# 2xVCA.net
KiCad netlist of a schematic drawn in EAGLE
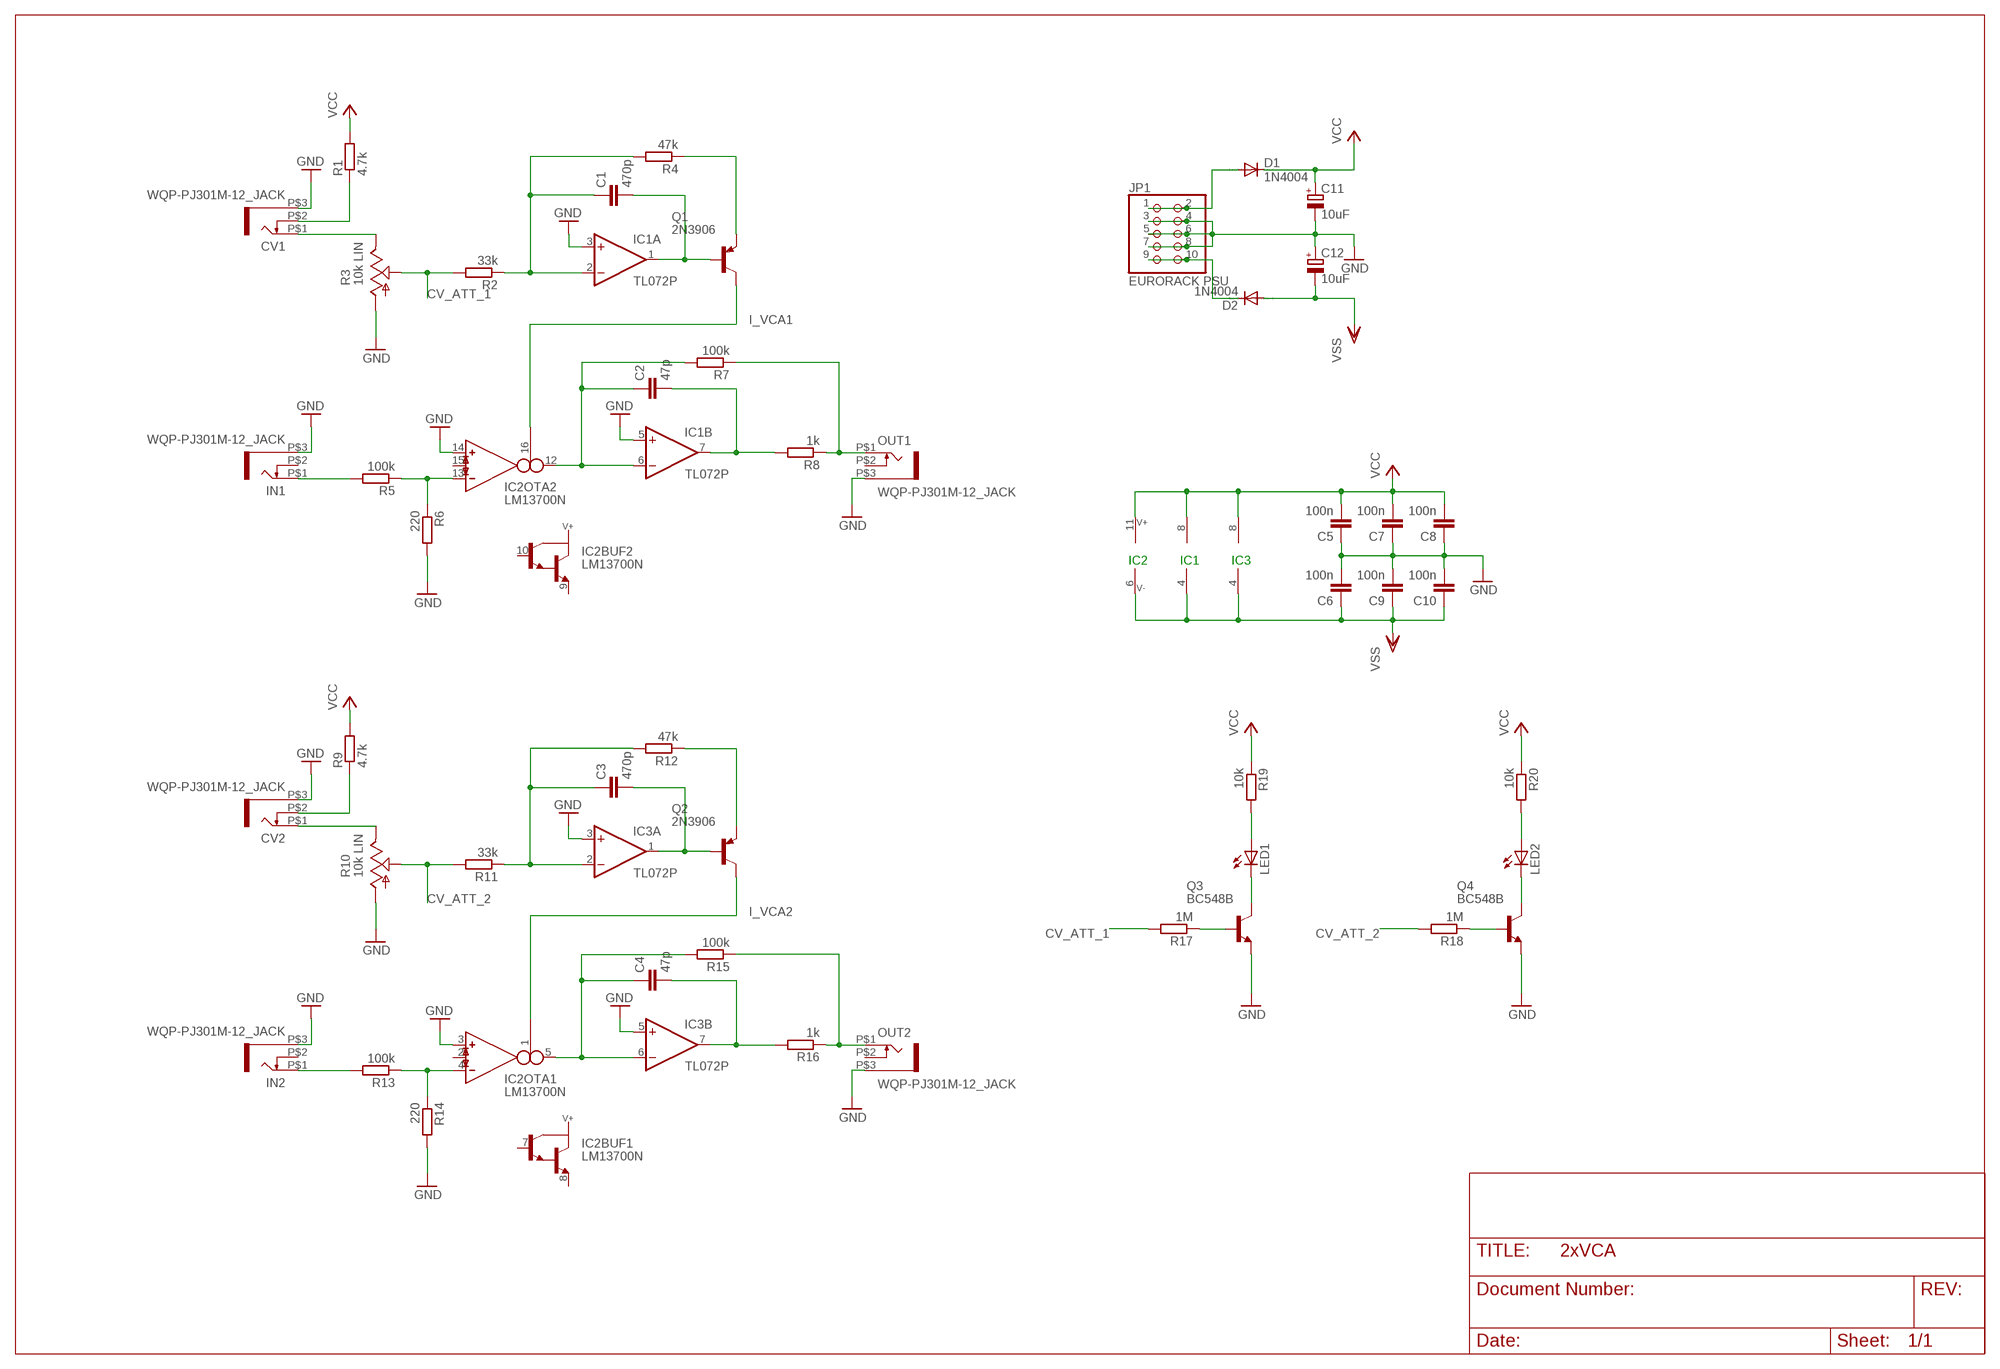
[diagram p0: schematic, sheet 1]

(export (version "E")
  (design (tool "Eeschema 10.0.6"))
  (components
    (comp (ref "C1")
      (value "470p")
      (footprint "eagle-import:C025-025X050")
      (libsource (lib "eagle-import") (part "C-EU025-025X050"))
    )
    (comp (ref "C2")
      (value "47p")
      (footprint "eagle-import:C025-025X050")
      (libsource (lib "eagle-import") (part "C-EU025-025X050"))
    )
    (comp (ref "C3")
      (value "470p")
      (footprint "eagle-import:C025-025X050")
      (libsource (lib "eagle-import") (part "C-EU025-025X050"))
    )
    (comp (ref "C4")
      (value "47p")
      (footprint "eagle-import:C025-025X050")
      (libsource (lib "eagle-import") (part "C-EU025-025X050"))
    )
    (comp (ref "C5")
      (value "100n")
      (footprint "eagle-import:C025-025X050")
      (libsource (lib "eagle-import") (part "C-EU025-025X050"))
    )
    (comp (ref "C6")
      (value "100n")
      (footprint "eagle-import:C025-025X050")
      (libsource (lib "eagle-import") (part "C-EU025-025X050"))
    )
    (comp (ref "C7")
      (value "100n")
      (footprint "eagle-import:C025-025X050")
      (libsource (lib "eagle-import") (part "C-EU025-025X050"))
    )
    (comp (ref "C8")
      (value "100n")
      (footprint "eagle-import:C025-025X050")
      (libsource (lib "eagle-import") (part "C-EU025-025X050"))
    )
    (comp (ref "C9")
      (value "100n")
      (footprint "eagle-import:C025-025X050")
      (libsource (lib "eagle-import") (part "C-EU025-025X050"))
    )
    (comp (ref "C10")
      (value "100n")
      (footprint "eagle-import:C025-025X050")
      (libsource (lib "eagle-import") (part "C-EU025-025X050"))
    )
    (comp (ref "C11")
      (value "10uF")
      (footprint "eagle-import:E2,5-5")
      (libsource (lib "eagle-import") (part "CPOL-EUE2.5-5"))
    )
    (comp (ref "C12")
      (value "10uF")
      (footprint "eagle-import:E2,5-5")
      (libsource (lib "eagle-import") (part "CPOL-EUE2.5-5"))
    )
    (comp (ref "CV1")
      (value "WQP-PJ301M-12_JACK")
      (footprint "eagle-import:WQP-PJ301M-12_JACK")
      (libsource (lib "eagle-import") (part "WQP-PJ301M-12_JACK"))
    )
    (comp (ref "CV2")
      (value "WQP-PJ301M-12_JACK")
      (footprint "eagle-import:WQP-PJ301M-12_JACK")
      (libsource (lib "eagle-import") (part "WQP-PJ301M-12_JACK"))
    )
    (comp (ref "D1")
      (value "1N4004")
      (footprint "eagle-import:DO41-10")
      (libsource (lib "eagle-import") (part "1N4004"))
    )
    (comp (ref "D2")
      (value "1N4004")
      (footprint "eagle-import:DO41-10")
      (libsource (lib "eagle-import") (part "1N4004"))
    )
    (comp (ref "IC1")
      (value "TL072P")
      (footprint "eagle-import:DIL08")
      (libsource (lib "eagle-import") (part "TL072P"))
    )
    (comp (ref "IC2")
      (value "LM13700N")
      (footprint "eagle-import:DIL16")
      (libsource (lib "eagle-import") (part "LM13700N"))
    )
    (comp (ref "IC3")
      (value "TL072P")
      (footprint "eagle-import:DIL08")
      (libsource (lib "eagle-import") (part "TL072P"))
    )
    (comp (ref "IN1")
      (value "WQP-PJ301M-12_JACK")
      (footprint "eagle-import:WQP-PJ301M-12_JACK")
      (libsource (lib "eagle-import") (part "WQP-PJ301M-12_JACK"))
    )
    (comp (ref "IN2")
      (value "WQP-PJ301M-12_JACK")
      (footprint "eagle-import:WQP-PJ301M-12_JACK")
      (libsource (lib "eagle-import") (part "WQP-PJ301M-12_JACK"))
    )
    (comp (ref "JP1")
      (value "EURORACK PSU")
      (footprint "eagle-import:2X05")
      (libsource (lib "eagle-import") (part "PINHD-2X5"))
    )
    (comp (ref "LED1")
      (value "LED3MM")
      (footprint "eagle-import:LED3MM")
      (libsource (lib "eagle-import") (part "LED3MM"))
    )
    (comp (ref "LED2")
      (value "LED3MM")
      (footprint "eagle-import:LED3MM")
      (libsource (lib "eagle-import") (part "LED3MM"))
    )
    (comp (ref "OUT1")
      (value "WQP-PJ301M-12_JACK")
      (footprint "eagle-import:WQP-PJ301M-12_JACK")
      (libsource (lib "eagle-import") (part "WQP-PJ301M-12_JACK"))
    )
    (comp (ref "OUT2")
      (value "WQP-PJ301M-12_JACK")
      (footprint "eagle-import:WQP-PJ301M-12_JACK")
      (libsource (lib "eagle-import") (part "WQP-PJ301M-12_JACK"))
    )
    (comp (ref "Q1")
      (value "2N3906")
      (footprint "eagle-import:TO92")
      (libsource (lib "eagle-import") (part "2N3906"))
    )
    (comp (ref "Q2")
      (value "2N3906")
      (footprint "eagle-import:TO92")
      (libsource (lib "eagle-import") (part "2N3906"))
    )
    (comp (ref "Q3")
      (value "BC548B")
      (footprint "eagle-import:TO92-EBC")
      (libsource (lib "eagle-import") (part "BC548B"))
    )
    (comp (ref "Q4")
      (value "BC548B")
      (footprint "eagle-import:TO92-EBC")
      (libsource (lib "eagle-import") (part "BC548B"))
    )
    (comp (ref "R1")
      (value "4.7k")
      (footprint "eagle-import:0207_2V")
      (libsource (lib "eagle-import") (part "R-EU_0207/2V"))
    )
    (comp (ref "R2")
      (value "33k")
      (footprint "eagle-import:0207_2V")
      (libsource (lib "eagle-import") (part "R-EU_0207/2V"))
    )
    (comp (ref "R3")
      (value "10k LIN")
      (footprint "eagle-import:ALPS_POT_VERTICAL")
      (libsource (lib "eagle-import") (part "POT_USVERTICAL"))
    )
    (comp (ref "R4")
      (value "47k")
      (footprint "eagle-import:0207_2V")
      (libsource (lib "eagle-import") (part "R-EU_0207/2V"))
    )
    (comp (ref "R5")
      (value "100k")
      (footprint "eagle-import:0207_2V")
      (libsource (lib "eagle-import") (part "R-EU_0207/2V"))
    )
    (comp (ref "R6")
      (value "220")
      (footprint "eagle-import:0207_2V")
      (libsource (lib "eagle-import") (part "R-EU_0207/2V"))
    )
    (comp (ref "R7")
      (value "100k")
      (footprint "eagle-import:0207_2V")
      (libsource (lib "eagle-import") (part "R-EU_0207/2V"))
    )
    (comp (ref "R8")
      (value "1k")
      (footprint "eagle-import:0207_2V")
      (libsource (lib "eagle-import") (part "R-EU_0207/2V"))
    )
    (comp (ref "R9")
      (value "4.7k")
      (footprint "eagle-import:0207_2V")
      (libsource (lib "eagle-import") (part "R-EU_0207/2V"))
    )
    (comp (ref "R10")
      (value "10k LIN")
      (footprint "eagle-import:ALPS_POT_VERTICAL")
      (libsource (lib "eagle-import") (part "POT_USVERTICAL"))
    )
    (comp (ref "R11")
      (value "33k")
      (footprint "eagle-import:0207_2V")
      (libsource (lib "eagle-import") (part "R-EU_0207/2V"))
    )
    (comp (ref "R12")
      (value "47k")
      (footprint "eagle-import:0207_2V")
      (libsource (lib "eagle-import") (part "R-EU_0207/2V"))
    )
    (comp (ref "R13")
      (value "100k")
      (footprint "eagle-import:0207_2V")
      (libsource (lib "eagle-import") (part "R-EU_0207/2V"))
    )
    (comp (ref "R14")
      (value "220")
      (footprint "eagle-import:0207_2V")
      (libsource (lib "eagle-import") (part "R-EU_0207/2V"))
    )
    (comp (ref "R15")
      (value "100k")
      (footprint "eagle-import:0207_2V")
      (libsource (lib "eagle-import") (part "R-EU_0207/2V"))
    )
    (comp (ref "R16")
      (value "1k")
      (footprint "eagle-import:0207_2V")
      (libsource (lib "eagle-import") (part "R-EU_0207/2V"))
    )
    (comp (ref "R17")
      (value "1M")
      (footprint "eagle-import:0207_2V")
      (libsource (lib "eagle-import") (part "R-EU_0207/2V"))
    )
    (comp (ref "R18")
      (value "1M")
      (footprint "eagle-import:0207_2V")
      (libsource (lib "eagle-import") (part "R-EU_0207/2V"))
    )
    (comp (ref "R19")
      (value "10k")
      (footprint "eagle-import:0207_2V")
      (libsource (lib "eagle-import") (part "R-EU_0207/2V"))
    )
    (comp (ref "R20")
      (value "10k")
      (footprint "eagle-import:0207_2V")
      (libsource (lib "eagle-import") (part "R-EU_0207/2V"))
    )
  )
  (nets
    (net (code "1") (name "/CV_ATT_1") (class "Default")
      (node (ref "R17") (pin "2") (pinfunction "2_2") (pintype "passive"))
      (node (ref "R2") (pin "2") (pinfunction "2_2") (pintype "passive"))
      (node (ref "R3") (pin "P$2") (pinfunction "S_P$2") (pintype "passive"))
    )
    (net (code "2") (name "/CV_ATT_2") (class "Default")
      (node (ref "R10") (pin "P$2") (pinfunction "S_P$2") (pintype "passive"))
      (node (ref "R11") (pin "2") (pinfunction "2_2") (pintype "passive"))
      (node (ref "R18") (pin "2") (pinfunction "2_2") (pintype "passive"))
    )
    (net (code "3") (name "/I_VCA1") (class "Default")
      (node (ref "IC2") (pin "16") (pinfunction "I_BIAS_16") (pintype "input"))
      (node (ref "Q1") (pin "1") (pinfunction "C_1") (pintype "passive"))
    )
    (net (code "4") (name "/I_VCA2") (class "Default")
      (node (ref "IC2") (pin "1") (pinfunction "I_BIAS_1") (pintype "input"))
      (node (ref "Q2") (pin "1") (pinfunction "C_1") (pintype "passive"))
    )
    (net (code "5") (name "GND") (class "Default")
      (node (ref "C10") (pin "2") (pinfunction "2_2") (pintype "passive"))
      (node (ref "C11") (pin "-") (pinfunction "-_-") (pintype "passive"))
      (node (ref "C12") (pin "+") (pinfunction "+_+") (pintype "passive"))
      (node (ref "C5") (pin "1") (pinfunction "1_1") (pintype "passive"))
      (node (ref "C6") (pin "2") (pinfunction "2_2") (pintype "passive"))
      (node (ref "C7") (pin "1") (pinfunction "1_1") (pintype "passive"))
      (node (ref "C8") (pin "1") (pinfunction "1_1") (pintype "passive"))
      (node (ref "C9") (pin "2") (pinfunction "2_2") (pintype "passive"))
      (node (ref "CV1") (pin "P$3") (pinfunction "1_P$3") (pintype "passive"))
      (node (ref "CV2") (pin "P$3") (pinfunction "1_P$3") (pintype "passive"))
      (node (ref "IC1") (pin "3") (pinfunction "+IN_3") (pintype "input"))
      (node (ref "IC1") (pin "5") (pinfunction "+IN_5") (pintype "input"))
      (node (ref "IC2") (pin "14") (pinfunction "IN_P_14") (pintype "input"))
      (node (ref "IC2") (pin "3") (pinfunction "IN_P_3") (pintype "input"))
      (node (ref "IC3") (pin "3") (pinfunction "+IN_3") (pintype "input"))
      (node (ref "IC3") (pin "5") (pinfunction "+IN_5") (pintype "input"))
      (node (ref "IN1") (pin "P$3") (pinfunction "1_P$3") (pintype "passive"))
      (node (ref "IN2") (pin "P$3") (pinfunction "1_P$3") (pintype "passive"))
      (node (ref "JP1") (pin "3") (pinfunction "3_3") (pintype "passive"))
      (node (ref "JP1") (pin "4") (pinfunction "4_4") (pintype "passive"))
      (node (ref "JP1") (pin "5") (pinfunction "5_5") (pintype "passive"))
      (node (ref "JP1") (pin "6") (pinfunction "6_6") (pintype "passive"))
      (node (ref "JP1") (pin "7") (pinfunction "7_7") (pintype "passive"))
      (node (ref "JP1") (pin "8") (pinfunction "8_8") (pintype "passive"))
      (node (ref "OUT1") (pin "P$3") (pinfunction "1_P$3") (pintype "passive"))
      (node (ref "OUT2") (pin "P$3") (pinfunction "1_P$3") (pintype "passive"))
      (node (ref "Q3") (pin "E") (pinfunction "E_E") (pintype "passive"))
      (node (ref "Q4") (pin "E") (pinfunction "E_E") (pintype "passive"))
      (node (ref "R10") (pin "P$3") (pinfunction "A_P$3") (pintype "passive"))
      (node (ref "R14") (pin "2") (pinfunction "2_2") (pintype "passive"))
      (node (ref "R3") (pin "P$3") (pinfunction "A_P$3") (pintype "passive"))
      (node (ref "R6") (pin "2") (pinfunction "2_2") (pintype "passive"))
    )
    (net (code "6") (name "Net-(CV1-2)") (class "Default")
      (node (ref "CV1") (pin "P$1") (pinfunction "2_P$1") (pintype "passive"))
      (node (ref "R3") (pin "P$1") (pinfunction "E_P$1") (pintype "passive"))
    )
    (net (code "7") (name "Net-(CV1-3)") (class "Default")
      (node (ref "CV1") (pin "P$2") (pinfunction "3_P$2") (pintype "passive"))
      (node (ref "R1") (pin "1") (pinfunction "1_1") (pintype "passive"))
    )
    (net (code "8") (name "Net-(CV2-2)") (class "Default")
      (node (ref "CV2") (pin "P$1") (pinfunction "2_P$1") (pintype "passive"))
      (node (ref "R10") (pin "P$1") (pinfunction "E_P$1") (pintype "passive"))
    )
    (net (code "9") (name "Net-(CV2-3)") (class "Default")
      (node (ref "CV2") (pin "P$2") (pinfunction "3_P$2") (pintype "passive"))
      (node (ref "R9") (pin "1") (pinfunction "1_1") (pintype "passive"))
    )
    (net (code "10") (name "Net-(D1-PadA)") (class "Default")
      (node (ref "D1") (pin "A") (pinfunction "A_A") (pintype "passive"))
      (node (ref "JP1") (pin "1") (pinfunction "1_1") (pintype "passive"))
      (node (ref "JP1") (pin "2") (pinfunction "2_2") (pintype "passive"))
    )
    (net (code "11") (name "Net-(D2-PadC)") (class "Default")
      (node (ref "D2") (pin "C") (pinfunction "C_C") (pintype "passive"))
      (node (ref "JP1") (pin "10") (pinfunction "10_10") (pintype "passive"))
      (node (ref "JP1") (pin "9") (pinfunction "9_9") (pintype "passive"))
    )
    (net (code "12") (name "Net-(IC1A--IN)") (class "Default")
      (node (ref "C1") (pin "1") (pinfunction "1_1") (pintype "passive"))
      (node (ref "IC1") (pin "2") (pinfunction "-IN_2") (pintype "input"))
      (node (ref "R2") (pin "1") (pinfunction "1_1") (pintype "passive"))
      (node (ref "R4") (pin "2") (pinfunction "2_2") (pintype "passive"))
    )
    (net (code "13") (name "Net-(IC1A-OUT)") (class "Default")
      (node (ref "C1") (pin "2") (pinfunction "2_2") (pintype "passive"))
      (node (ref "IC1") (pin "1") (pinfunction "OUT_1") (pintype "output"))
      (node (ref "Q1") (pin "2") (pinfunction "B_2") (pintype "passive"))
    )
    (net (code "14") (name "Net-(IC1B--IN)") (class "Default")
      (node (ref "C2") (pin "1") (pinfunction "1_1") (pintype "passive"))
      (node (ref "IC1") (pin "6") (pinfunction "-IN_6") (pintype "input"))
      (node (ref "IC2") (pin "12") (pinfunction "OUT_12") (pintype "output"))
      (node (ref "R7") (pin "2") (pinfunction "2_2") (pintype "passive"))
    )
    (net (code "15") (name "Net-(IC1B-OUT)") (class "Default")
      (node (ref "C2") (pin "2") (pinfunction "2_2") (pintype "passive"))
      (node (ref "IC1") (pin "7") (pinfunction "OUT_7") (pintype "output"))
      (node (ref "R8") (pin "2") (pinfunction "2_2") (pintype "passive"))
    )
    (net (code "16") (name "Net-(IC2C-IN_N)") (class "Default")
      (node (ref "IC2") (pin "4") (pinfunction "IN_N_4") (pintype "input"))
      (node (ref "R13") (pin "1") (pinfunction "1_1") (pintype "passive"))
      (node (ref "R14") (pin "1") (pinfunction "1_1") (pintype "passive"))
    )
    (net (code "17") (name "Net-(IC2C-OUT)") (class "Default")
      (node (ref "C4") (pin "1") (pinfunction "1_1") (pintype "passive"))
      (node (ref "IC2") (pin "5") (pinfunction "OUT_5") (pintype "output"))
      (node (ref "IC3") (pin "6") (pinfunction "-IN_6") (pintype "input"))
      (node (ref "R15") (pin "2") (pinfunction "2_2") (pintype "passive"))
    )
    (net (code "18") (name "Net-(IC2D-IN_N)") (class "Default")
      (node (ref "IC2") (pin "13") (pinfunction "IN_N_13") (pintype "input"))
      (node (ref "R5") (pin "1") (pinfunction "1_1") (pintype "passive"))
      (node (ref "R6") (pin "1") (pinfunction "1_1") (pintype "passive"))
    )
    (net (code "19") (name "Net-(IC3A--IN)") (class "Default")
      (node (ref "C3") (pin "1") (pinfunction "1_1") (pintype "passive"))
      (node (ref "IC3") (pin "2") (pinfunction "-IN_2") (pintype "input"))
      (node (ref "R11") (pin "1") (pinfunction "1_1") (pintype "passive"))
      (node (ref "R12") (pin "2") (pinfunction "2_2") (pintype "passive"))
    )
    (net (code "20") (name "Net-(IC3A-OUT)") (class "Default")
      (node (ref "C3") (pin "2") (pinfunction "2_2") (pintype "passive"))
      (node (ref "IC3") (pin "1") (pinfunction "OUT_1") (pintype "output"))
      (node (ref "Q2") (pin "2") (pinfunction "B_2") (pintype "passive"))
    )
    (net (code "21") (name "Net-(IC3B-OUT)") (class "Default")
      (node (ref "C4") (pin "2") (pinfunction "2_2") (pintype "passive"))
      (node (ref "IC3") (pin "7") (pinfunction "OUT_7") (pintype "output"))
      (node (ref "R16") (pin "2") (pinfunction "2_2") (pintype "passive"))
    )
    (net (code "22") (name "Net-(IN1-2)") (class "Default")
      (node (ref "IN1") (pin "P$1") (pinfunction "2_P$1") (pintype "passive"))
      (node (ref "R5") (pin "2") (pinfunction "2_2") (pintype "passive"))
    )
    (net (code "23") (name "Net-(IN2-2)") (class "Default")
      (node (ref "IN2") (pin "P$1") (pinfunction "2_P$1") (pintype "passive"))
      (node (ref "R13") (pin "2") (pinfunction "2_2") (pintype "passive"))
    )
    (net (code "24") (name "Net-(LED1-C)") (class "Default")
      (node (ref "LED1") (pin "K") (pinfunction "C_K") (pintype "passive"))
      (node (ref "Q3") (pin "C") (pinfunction "C_C") (pintype "passive"))
    )
    (net (code "25") (name "Net-(LED1-PadA)") (class "Default")
      (node (ref "LED1") (pin "A") (pinfunction "A_A") (pintype "passive"))
      (node (ref "R19") (pin "2") (pinfunction "2_2") (pintype "passive"))
    )
    (net (code "26") (name "Net-(LED2-C)") (class "Default")
      (node (ref "LED2") (pin "K") (pinfunction "C_K") (pintype "passive"))
      (node (ref "Q4") (pin "C") (pinfunction "C_C") (pintype "passive"))
    )
    (net (code "27") (name "Net-(LED2-PadA)") (class "Default")
      (node (ref "LED2") (pin "A") (pinfunction "A_A") (pintype "passive"))
      (node (ref "R20") (pin "2") (pinfunction "2_2") (pintype "passive"))
    )
    (net (code "28") (name "Net-(OUT1-2)") (class "Default")
      (node (ref "OUT1") (pin "P$1") (pinfunction "2_P$1") (pintype "passive"))
      (node (ref "R7") (pin "1") (pinfunction "1_1") (pintype "passive"))
      (node (ref "R8") (pin "1") (pinfunction "1_1") (pintype "passive"))
    )
    (net (code "29") (name "Net-(OUT2-2)") (class "Default")
      (node (ref "OUT2") (pin "P$1") (pinfunction "2_P$1") (pintype "passive"))
      (node (ref "R15") (pin "1") (pinfunction "1_1") (pintype "passive"))
      (node (ref "R16") (pin "1") (pinfunction "1_1") (pintype "passive"))
    )
    (net (code "30") (name "Net-(Q1-E)") (class "Default")
      (node (ref "Q1") (pin "3") (pinfunction "E_3") (pintype "passive"))
      (node (ref "R4") (pin "1") (pinfunction "1_1") (pintype "passive"))
    )
    (net (code "31") (name "Net-(Q2-E)") (class "Default")
      (node (ref "Q2") (pin "3") (pinfunction "E_3") (pintype "passive"))
      (node (ref "R12") (pin "1") (pinfunction "1_1") (pintype "passive"))
    )
    (net (code "32") (name "Net-(Q3-PadB)") (class "Default")
      (node (ref "Q3") (pin "B") (pinfunction "B_B") (pintype "passive"))
      (node (ref "R17") (pin "1") (pinfunction "1_1") (pintype "passive"))
    )
    (net (code "33") (name "Net-(Q4-PadB)") (class "Default")
      (node (ref "Q4") (pin "B") (pinfunction "B_B") (pintype "passive"))
      (node (ref "R18") (pin "1") (pinfunction "1_1") (pintype "passive"))
    )
    (net (code "34") (name "VCC") (class "Default")
      (node (ref "C11") (pin "+") (pinfunction "+_+") (pintype "passive"))
      (node (ref "C5") (pin "2") (pinfunction "2_2") (pintype "passive"))
      (node (ref "C7") (pin "2") (pinfunction "2_2") (pintype "passive"))
      (node (ref "C8") (pin "2") (pinfunction "2_2") (pintype "passive"))
      (node (ref "D1") (pin "C") (pinfunction "C_C") (pintype "passive"))
      (node (ref "IC1") (pin "8") (pinfunction "V+_8") (pintype "power_in"))
      (node (ref "IC2") (pin "11") (pinfunction "V+_11") (pintype "power_in"))
      (node (ref "IC3") (pin "8") (pinfunction "V+_8") (pintype "power_in"))
      (node (ref "R1") (pin "2") (pinfunction "2_2") (pintype "passive"))
      (node (ref "R19") (pin "1") (pinfunction "1_1") (pintype "passive"))
      (node (ref "R20") (pin "1") (pinfunction "1_1") (pintype "passive"))
      (node (ref "R9") (pin "2") (pinfunction "2_2") (pintype "passive"))
    )
    (net (code "35") (name "VSS") (class "Default")
      (node (ref "C10") (pin "1") (pinfunction "1_1") (pintype "passive"))
      (node (ref "C12") (pin "-") (pinfunction "-_-") (pintype "passive"))
      (node (ref "C6") (pin "1") (pinfunction "1_1") (pintype "passive"))
      (node (ref "C9") (pin "1") (pinfunction "1_1") (pintype "passive"))
      (node (ref "D2") (pin "A") (pinfunction "A_A") (pintype "passive"))
      (node (ref "IC1") (pin "4") (pinfunction "V-_4") (pintype "power_in"))
      (node (ref "IC2") (pin "6") (pinfunction "V-_6") (pintype "power_in"))
      (node (ref "IC3") (pin "4") (pinfunction "V-_4") (pintype "power_in"))
    )
    (net (code "36") (name "unconnected-(IC2A-B-Pad7)") (class "Default")
      (node (ref "IC2") (pin "7") (pinfunction "B_7") (pintype "passive"))
    )
    (net (code "37") (name "unconnected-(IC2A-E-Pad8)") (class "Default")
      (node (ref "IC2") (pin "8") (pinfunction "E_8") (pintype "passive"))
    )
    (net (code "38") (name "unconnected-(IC2B-B-Pad10)") (class "Default")
      (node (ref "IC2") (pin "10") (pinfunction "B_10") (pintype "passive"))
    )
    (net (code "39") (name "unconnected-(IC2B-E-Pad9)") (class "Default")
      (node (ref "IC2") (pin "9") (pinfunction "E_9") (pintype "passive"))
    )
    (net (code "40") (name "unconnected-(IC2C-I_DIODE-Pad2)") (class "Default")
      (node (ref "IC2") (pin "2") (pinfunction "I_DIODE_2") (pintype "input"))
    )
    (net (code "41") (name "unconnected-(IC2D-I_DIODE-Pad15)") (class "Default")
      (node (ref "IC2") (pin "15") (pinfunction "I_DIODE_15") (pintype "input"))
    )
    (net (code "42") (name "unconnected-(IN1-3-PadP$2)") (class "Default")
      (node (ref "IN1") (pin "P$2") (pinfunction "3_P$2") (pintype "passive"))
    )
    (net (code "43") (name "unconnected-(IN2-3-PadP$2)") (class "Default")
      (node (ref "IN2") (pin "P$2") (pinfunction "3_P$2") (pintype "passive"))
    )
    (net (code "44") (name "unconnected-(OUT1-3-PadP$2)") (class "Default")
      (node (ref "OUT1") (pin "P$2") (pinfunction "3_P$2") (pintype "passive"))
    )
    (net (code "45") (name "unconnected-(OUT2-3-PadP$2)") (class "Default")
      (node (ref "OUT2") (pin "P$2") (pinfunction "3_P$2") (pintype "passive"))
    )
  )
)
